# 40V_Output_Design.net
KiCad netlist of a schematic drawn in Altium Designer
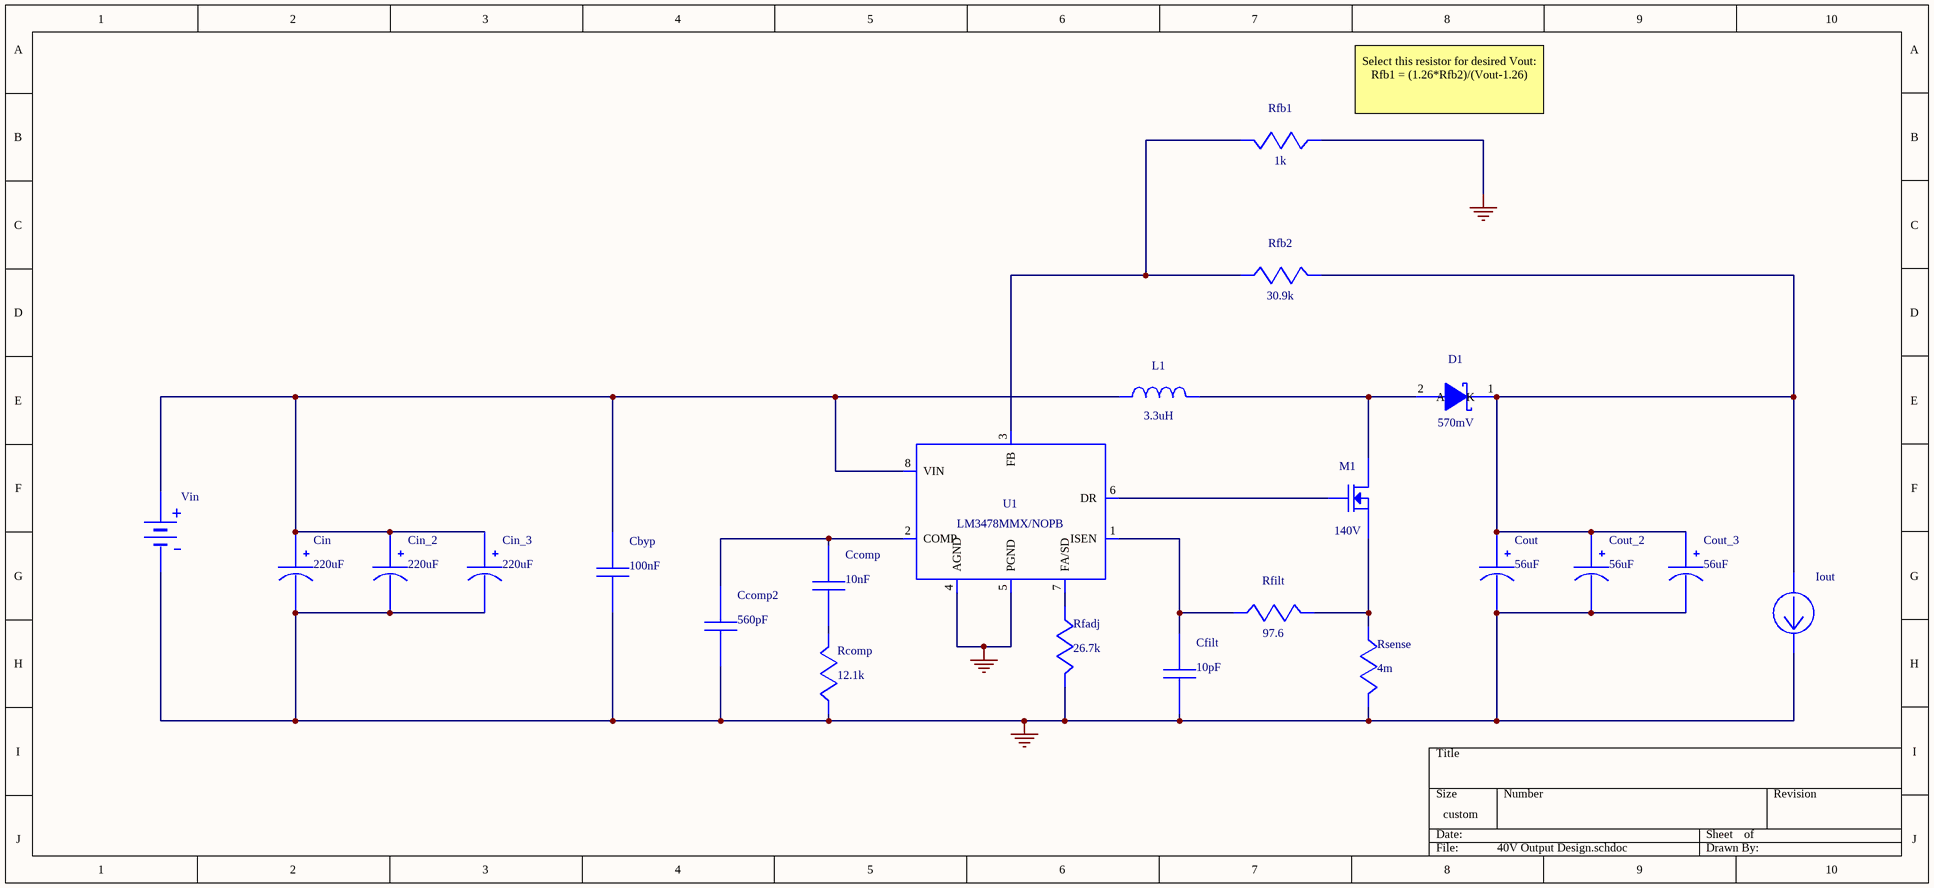
[diagram p0: 40V Output Design.schdoc]

(export (version "E")
  (design (tool "Eeschema 10.0.6"))
  (components
    (comp (ref "Cbyp")
      (value "100nF")
      (description "GRM155R70J104KA0")
      (fields (field (name "MANUFACTURER PART NUMBER") "GRM155R70J104KA01D"))
      (libsource (lib "TI WEBENCH") (part "Cbyp"))
    )
    (comp (ref "Ccomp")
      (value "10nF")
      (description "C2012C0G1H103K06")
      (fields (field (name "MANUFACTURER PART NUMBER") "C2012C0G1H103K060AA"))
      (libsource (lib "TI WEBENCH") (part "Ccomp"))
    )
    (comp (ref "Ccomp2")
      (value "560pF")
      (description "GRM1555C1H561JA0")
      (fields (field (name "MANUFACTURER PART NUMBER") "GRM1555C1H561JA01J"))
      (libsource (lib "TI WEBENCH") (part "Ccomp2"))
    )
    (comp (ref "Cfilt")
      (value "10pF")
      (description "CL21C100JBANNNC")
      (libsource (lib "TI WEBENCH") (part "Cfilt"))
    )
    (comp (ref "Cin") (value "220uF") (description "6SVPE220MW") (libsource (lib "TI WEBENCH") (part "Cin")))
    (comp (ref "Cin_2")
      (value "220uF")
      (description "6SVPE220MW")
      (libsource (lib "TI WEBENCH") (part "Cin_2"))
    )
    (comp (ref "Cin_3")
      (value "220uF")
      (description "6SVPE220MW")
      (libsource (lib "TI WEBENCH") (part "Cin_3"))
    )
    (comp (ref "Cout")
      (value "56uF")
      (description "EEHZA1J560P")
      (libsource (lib "TI WEBENCH") (part "Cout"))
    )
    (comp (ref "Cout_2")
      (value "56uF")
      (description "EEHZA1J560P")
      (libsource (lib "TI WEBENCH") (part "Cout_2"))
    )
    (comp (ref "Cout_3")
      (value "56uF")
      (description "EEHZA1J560P")
      (libsource (lib "TI WEBENCH") (part "Cout_3"))
    )
    (comp (ref "D1")
      (value "570mV")
      (description "PMEG6010CEH,115")
      (libsource (lib "TI WEBENCH") (part "D1"))
    )
    (comp (ref "Iout") (value "WB_CURRENT_LOAD") (libsource (lib "TI WEBENCH") (part "Iout")))
    (comp (ref "L1") (value "3.3uH") (description "SRP1235-3R3M") (libsource (lib "TI WEBENCH") (part "L1")))
    (comp (ref "M1")
      (value "140V")
      (description "IdealFET")
      (fields (field (name "MANUFACTURER PART NUMBER") "GENERIC_MOSFET_N"))
      (libsource (lib "TI WEBENCH") (part "M1"))
    )
    (comp (ref "Rcomp")
      (value "12.1k")
      (description "RC0201FR-0712K1L")
      (libsource (lib "TI WEBENCH") (part "Rcomp"))
    )
    (comp (ref "Rfadj")
      (value "26.7k")
      (description "CRCW040226K7FKED")
      (libsource (lib "TI WEBENCH") (part "Rfadj"))
    )
    (comp (ref "Rfb1")
      (value "1k")
      (description "RC0603FR-071KL")
      (libsource (lib "TI WEBENCH") (part "Rfb1"))
    )
    (comp (ref "Rfb2")
      (value "30.9k")
      (description "CRCW040230K9FKED")
      (libsource (lib "TI WEBENCH") (part "Rfb2"))
    )
    (comp (ref "Rfilt")
      (value "97.6")
      (description "CRCW040297R6FKED")
      (libsource (lib "TI WEBENCH") (part "Rfilt"))
    )
    (comp (ref "Rsense")
      (value "4m")
      (description "ERJ-M1WSF4M0U")
      (libsource (lib "TI WEBENCH") (part "Rsense"))
    )
    (comp (ref "U1")
      (value "LM3478MM/NOPB")
      (description "LM3478MMX/NOPB")
      (fields (field (name "PACKAGEREFERENCE") "LM3478MMX/NOPB"))
      (libsource (lib "TI WEBENCH") (part "U1"))
    )
    (comp (ref "Vin") (value "WB_BATTERY") (libsource (lib "TI WEBENCH") (part "Vin")))
  )
  (nets
    (net (code "1") (name "0") (class "Default")
      (node (ref "Cbyp") (pin "2") (pinfunction "2_2") (pintype "passive"))
      (node (ref "Ccomp2") (pin "2") (pinfunction "2_2") (pintype "passive"))
      (node (ref "Cfilt") (pin "2") (pinfunction "2_2") (pintype "passive"))
      (node (ref "Cin") (pin "2") (pinfunction "-_2") (pintype "passive"))
      (node (ref "Cin_2") (pin "2") (pinfunction "-_2") (pintype "passive"))
      (node (ref "Cin_3") (pin "2") (pinfunction "-_2") (pintype "passive"))
      (node (ref "Cout") (pin "2") (pinfunction "-_2") (pintype "passive"))
      (node (ref "Cout_2") (pin "2") (pinfunction "-_2") (pintype "passive"))
      (node (ref "Cout_3") (pin "2") (pinfunction "-_2") (pintype "passive"))
      (node (ref "Iout") (pin "2") (pinfunction "-_2") (pintype "passive"))
      (node (ref "Rcomp") (pin "2") (pinfunction "2_2") (pintype "passive"))
      (node (ref "Rfadj") (pin "1") (pinfunction "1_1") (pintype "passive"))
      (node (ref "Rfb1") (pin "2") (pinfunction "2_2") (pintype "passive"))
      (node (ref "Rsense") (pin "1") (pinfunction "1_1") (pintype "passive"))
      (node (ref "U1") (pin "4") (pinfunction "AGND_4") (pintype "passive"))
      (node (ref "U1") (pin "5") (pinfunction "PGND_5") (pintype "passive"))
      (node (ref "Vin") (pin "2") (pinfunction "-_2") (pintype "passive"))
    )
    (net (code "2") (name "Net-(Ccomp-Pad2)") (class "Default")
      (node (ref "Ccomp") (pin "2") (pinfunction "2_2") (pintype "passive"))
      (node (ref "Rcomp") (pin "1") (pinfunction "1_1") (pintype "passive"))
    )
    (net (code "3") (name "Net-(Cin-+)") (class "Default")
      (node (ref "Cbyp") (pin "1") (pinfunction "1_1") (pintype "passive"))
      (node (ref "Cin") (pin "1") (pinfunction "+_1") (pintype "passive"))
      (node (ref "Cin_2") (pin "1") (pinfunction "+_1") (pintype "passive"))
      (node (ref "Cin_3") (pin "1") (pinfunction "+_1") (pintype "passive"))
      (node (ref "L1") (pin "1") (pinfunction "1_1") (pintype "passive"))
      (node (ref "U1") (pin "8") (pinfunction "VIN_8") (pintype "passive"))
      (node (ref "Vin") (pin "1") (pinfunction "+_1") (pintype "passive"))
    )
    (net (code "4") (name "Net-(Cout-+)") (class "Default")
      (node (ref "Cout") (pin "1") (pinfunction "+_1") (pintype "passive"))
      (node (ref "Cout_2") (pin "1") (pinfunction "+_1") (pintype "passive"))
      (node (ref "Cout_3") (pin "1") (pinfunction "+_1") (pintype "passive"))
      (node (ref "D1") (pin "1") (pinfunction "K_1") (pintype "passive"))
      (node (ref "Iout") (pin "1") (pinfunction "+_1") (pintype "passive"))
      (node (ref "Rfb2") (pin "1") (pinfunction "1_1") (pintype "passive"))
    )
    (net (code "5") (name "Net-(D1-A)") (class "Default")
      (node (ref "D1") (pin "2") (pinfunction "A_2") (pintype "passive"))
      (node (ref "L1") (pin "2") (pinfunction "2_2") (pintype "passive"))
      (node (ref "M1") (pin "2") (pinfunction "Drain_2") (pintype "passive"))
    )
    (net (code "6") (name "Net-(M1-Gate)") (class "Default")
      (node (ref "M1") (pin "1") (pinfunction "Gate_1") (pintype "passive"))
      (node (ref "U1") (pin "6") (pinfunction "DR_6") (pintype "passive"))
    )
    (net (code "7") (name "Net-(M1-Source)") (class "Default")
      (node (ref "M1") (pin "3") (pinfunction "Source_3") (pintype "passive"))
      (node (ref "Rfilt") (pin "1") (pinfunction "1_1") (pintype "passive"))
      (node (ref "Rsense") (pin "2") (pinfunction "2_2") (pintype "passive"))
    )
    (net (code "8") (name "Net-(U1-COMP)") (class "Default")
      (node (ref "Ccomp") (pin "1") (pinfunction "1_1") (pintype "passive"))
      (node (ref "Ccomp2") (pin "1") (pinfunction "1_1") (pintype "passive"))
      (node (ref "U1") (pin "2") (pinfunction "COMP_2") (pintype "passive"))
    )
    (net (code "9") (name "Net-(U1-FA{slash}SD)") (class "Default")
      (node (ref "Rfadj") (pin "2") (pinfunction "2_2") (pintype "passive"))
      (node (ref "U1") (pin "7") (pinfunction "FA/SD_7") (pintype "passive"))
    )
    (net (code "10") (name "Net-(U1-FB)") (class "Default")
      (node (ref "Rfb1") (pin "1") (pinfunction "1_1") (pintype "passive"))
      (node (ref "Rfb2") (pin "2") (pinfunction "2_2") (pintype "passive"))
      (node (ref "U1") (pin "3") (pinfunction "FB_3") (pintype "passive"))
    )
    (net (code "11") (name "Net-(U1-ISEN)") (class "Default")
      (node (ref "Cfilt") (pin "1") (pinfunction "1_1") (pintype "passive"))
      (node (ref "Rfilt") (pin "2") (pinfunction "2_2") (pintype "passive"))
      (node (ref "U1") (pin "1") (pinfunction "ISEN_1") (pintype "passive"))
    )
  )
)
